# MCU.net
KiCad netlist of a schematic drawn in Altium Designer
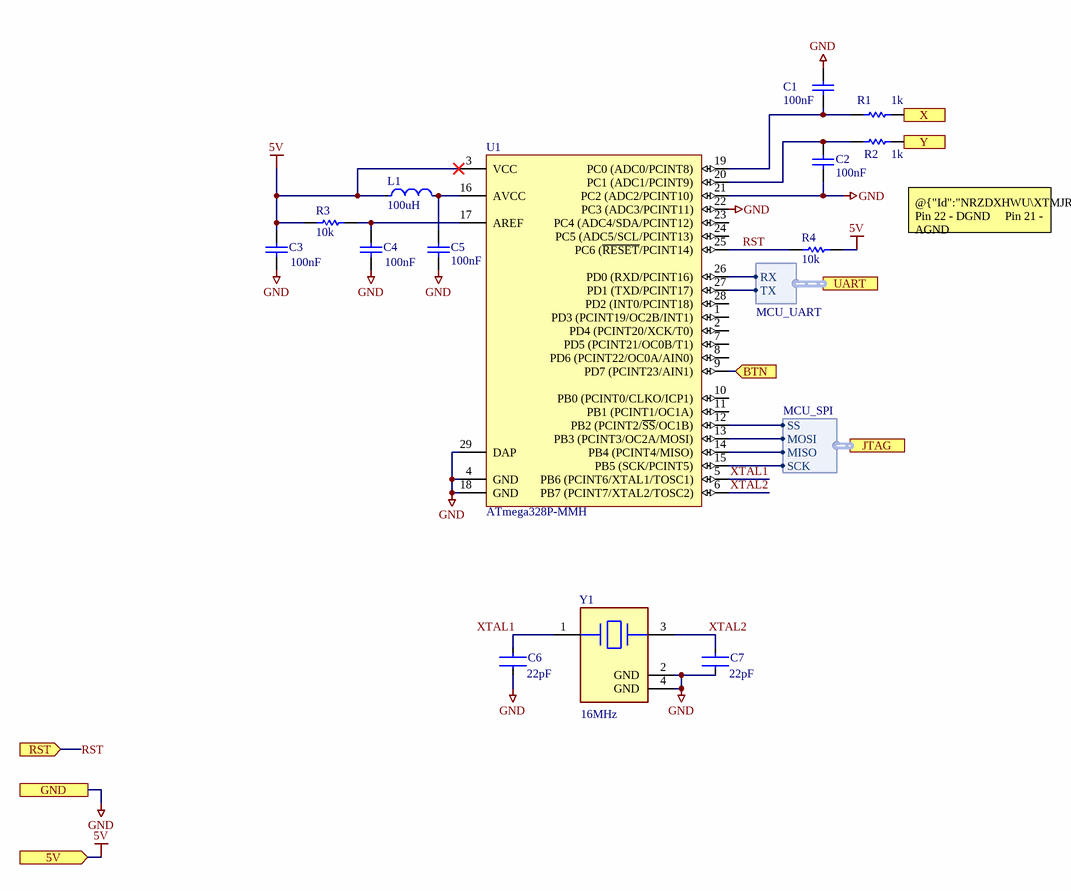
[diagram p0: MCU.SchDoc]

(export (version "E")
  (design (tool "Eeschema 10.0.6"))
  (components
    (comp (ref "C1")
      (value "100nF")
      (footprint "CAPC1005X56X25ML10T15")
      (fields
        (field (name "MANUFACTURER") "AVX Interconnect / Elco")
        (field (name "PART NUMBER") "0402YG104ZAT2A")
      )
      (libsource (lib "Altium Content Vault") (part "CAP"))
    )
    (comp (ref "C2")
      (value "100nF")
      (footprint "CAPC1005X56X25ML10T15")
      (fields
        (field (name "MANUFACTURER") "AVX Interconnect / Elco")
        (field (name "PART NUMBER") "0402YG104ZAT2A")
      )
      (libsource (lib "Altium Content Vault") (part "CAP"))
    )
    (comp (ref "C3")
      (value "100nF")
      (footprint "CAPC1005X56X25ML10T15")
      (fields
        (field (name "MANUFACTURER") "AVX Interconnect / Elco")
        (field (name "PART NUMBER") "0402YG104ZAT2A")
      )
      (libsource (lib "Altium Content Vault") (part "CAP"))
    )
    (comp (ref "C4")
      (value "100nF")
      (footprint "CAPC1005X56X25ML10T15")
      (fields
        (field (name "MANUFACTURER") "AVX Interconnect / Elco")
        (field (name "PART NUMBER") "0402YG104ZAT2A")
      )
      (libsource (lib "Altium Content Vault") (part "CAP"))
    )
    (comp (ref "C5")
      (value "100nF")
      (footprint "CAPC1005X56X25ML10T15")
      (fields
        (field (name "MANUFACTURER") "AVX Interconnect / Elco")
        (field (name "PART NUMBER") "0402YG104ZAT2A")
      )
      (libsource (lib "Altium Content Vault") (part "CAP"))
    )
    (comp (ref "C6")
      (value "C0805C220J5GACTU")
      (footprint "FP-C0805C-DN-MFG")
      (description "Capacitor; Ceramic; Cap; 22.0pF; Tol 5%; SMT; Vol-Rtg 50V; C0G; Tape and Reel")
      (fields
        (field (name "OCTOPART") "https://octopart.com/c0805c220j5gactu-kemet-145470")
        (field (name "MANUFACTURER") "KEMET")
      )
      (libsource (lib "Altium Content Vault") (part "b4654b650e69147ec39a6b967a45e02"))
    )
    (comp (ref "C7")
      (value "C0805C220J5GACTU")
      (footprint "FP-C0805C-DN-MFG")
      (description "Capacitor; Ceramic; Cap; 22.0pF; Tol 5%; SMT; Vol-Rtg 50V; C0G; Tape and Reel")
      (fields
        (field (name "OCTOPART") "https://octopart.com/c0805c220j5gactu-kemet-145470")
        (field (name "MANUFACTURER") "KEMET")
      )
      (libsource (lib "Altium Content Vault") (part "b4654b650e69147ec39a6b967a45e02"))
    )
    (comp (ref "L1")
      (value "100uH")
      (footprint "FP-CB3225-MFG")
      (description "SMD Inductors 100uH ±20% 0.34A 1.82Ω 1210")
      (fields (field (name "TOLERANCE") "20%"))
      (libsource (lib "Altium Content Vault") (part "725321dda6339637d4d059423bc1c3c"))
    )
    (comp (ref "R1")
      (value "1k")
      (footprint "RESC1608X55X25ML10T15")
      (fields (field (name "PART NUMBER") "RT0603BRE071KL") (field (name "MANUFACTURER") "Yageo"))
      (libsource (lib "Altium Content Vault") (part "RES"))
    )
    (comp (ref "R2")
      (value "1k")
      (footprint "RESC1608X55X25ML10T15")
      (fields (field (name "PART NUMBER") "RT0603BRE071KL") (field (name "MANUFACTURER") "Yageo"))
      (libsource (lib "Altium Content Vault") (part "RES"))
    )
    (comp (ref "R3")
      (value "10k")
      (footprint "RESC1005X40X25LL05T05")
      (description "Chip Resistor, 10 KOhm, +/- 1%, 0.1 W, -55 to 155 degC, 0402 (1005 Metric), RoHS, Tape and Reel")
      (fields (field (name "TOLERANCE") "1%") (field (name "MANUFACTURER") "Panasonic"))
      (libsource (lib "Altium Content Vault") (part "RES-2"))
    )
    (comp (ref "R4")
      (value "10k")
      (footprint "RESC1005X40X25LL05T05")
      (description "Chip Resistor, 10 KOhm, +/- 1%, 0.1 W, -55 to 155 degC, 0402 (1005 Metric), RoHS, Tape and Reel")
      (fields (field (name "TOLERANCE") "1%") (field (name "MANUFACTURER") "Panasonic"))
      (libsource (lib "Altium Content Vault") (part "RES-2"))
    )
    (comp (ref "U1")
      (value "ATmega328P-MMH")
      (footprint "28M1_N")
      (libsource (lib "Altium Content Vault") (part "MC-8B-ATM48-IL29"))
    )
    (comp (ref "Y1")
      (value "ABM3B-16.000MHZ-10-1-U-T")
      (footprint "FP-ABM3B-MFG")
      (description "Crystal 16MHz ±10ppm 10pF SMD-4 5mm x 3.2mm")
      (fields (field (name "TOLERANCE") "10ppm"))
      (libsource (lib "Altium Content Vault") (part "48e526d86b7f2615d98721063c72f49"))
    )
  )
  (nets
    (net (code "3") (name "/BTN") (class "Default")
      (node (ref "U1") (pin "9") (pinfunction "PD7_(PCINT23/AIN1)_9") (pintype "bidirectional"))
    )
    (net (code "4") (name "/MISO") (class "Default")
      (node (ref "U1") (pin "14") (pinfunction "PB4_(PCINT4/MISO)_14") (pintype "bidirectional"))
    )
    (net (code "5") (name "/MOSI") (class "Default")
      (node (ref "U1") (pin "13") (pinfunction "PB3_(PCINT3/OC2A/MOSI)_13") (pintype "bidirectional"))
    )
    (net (code "6") (name "/RST") (class "Default")
      (node (ref "R4") (pin "2") (pinfunction "2_2") (pintype "passive"))
      (node (ref "U1") (pin "25") (pinfunction "PC6_(~{RESET}/PCINT14)_25") (pintype "bidirectional"))
    )
    (net (code "7") (name "/RX") (class "Default")
      (node (ref "U1") (pin "26") (pinfunction "PD0_(RXD/PCINT16)_26") (pintype "bidirectional"))
    )
    (net (code "8") (name "/SCK") (class "Default")
      (node (ref "U1") (pin "15") (pinfunction "PB5_(SCK/PCINT5)_15") (pintype "bidirectional"))
    )
    (net (code "9") (name "/SS") (class "Default")
      (node (ref "U1") (pin "12") (pinfunction "PB2_(PCINT2/~{SS}/OC1B)_12") (pintype "bidirectional"))
    )
    (net (code "10") (name "/TX") (class "Default")
      (node (ref "U1") (pin "27") (pinfunction "PD1_(TXD/PCINT17)_27") (pintype "bidirectional"))
    )
    (net (code "11") (name "/X") (class "Default")
      (node (ref "R1") (pin "2") (pinfunction "2_2") (pintype "passive"))
    )
    (net (code "12") (name "/XTAL1") (class "Default")
      (node (ref "C6") (pin "1") (pinfunction "1_1") (pintype "passive"))
      (node (ref "U1") (pin "5") (pinfunction "PB6_(PCINT6/XTAL1/TOSC1)_5") (pintype "bidirectional"))
      (node (ref "Y1") (pin "1") (pinfunction "1_1") (pintype "passive"))
    )
    (net (code "13") (name "/XTAL2") (class "Default")
      (node (ref "C7") (pin "1") (pinfunction "1_1") (pintype "passive"))
      (node (ref "U1") (pin "6") (pinfunction "PB7_(PCINT7/XTAL2/TOSC2)_6") (pintype "bidirectional"))
      (node (ref "Y1") (pin "3") (pinfunction "3_3") (pintype "passive"))
    )
    (net (code "14") (name "/Y") (class "Default")
      (node (ref "R2") (pin "2") (pinfunction "2_2") (pintype "passive"))
    )
    (net (code "17") (name "5V") (class "Default")
      (node (ref "C3") (pin "2") (pinfunction "2_2") (pintype "passive"))
      (node (ref "L1") (pin "1") (pinfunction "1_1") (pintype "passive"))
      (node (ref "R3") (pin "2") (pinfunction "2_2") (pintype "passive"))
      (node (ref "R4") (pin "1") (pinfunction "1_1") (pintype "passive"))
      (node (ref "U1") (pin "3") (pinfunction "VCC_3") (pintype "power_in"))
    )
    (net (code "18") (name "GND") (class "Default")
      (node (ref "C1") (pin "2") (pinfunction "2_2") (pintype "passive"))
      (node (ref "C2") (pin "2") (pinfunction "2_2") (pintype "passive"))
      (node (ref "C3") (pin "1") (pinfunction "1_1") (pintype "passive"))
      (node (ref "C4") (pin "1") (pinfunction "1_1") (pintype "passive"))
      (node (ref "C5") (pin "2") (pinfunction "2_2") (pintype "passive"))
      (node (ref "C6") (pin "2") (pinfunction "2_2") (pintype "passive"))
      (node (ref "C7") (pin "2") (pinfunction "2_2") (pintype "passive"))
      (node (ref "U1") (pin "18") (pinfunction "GND_18") (pintype "power_in"))
      (node (ref "U1") (pin "21") (pinfunction "PC2_(ADC2/PCINT10)_21") (pintype "bidirectional"))
      (node (ref "U1") (pin "22") (pinfunction "PC3_(ADC3/PCINT11)_22") (pintype "bidirectional"))
      (node (ref "U1") (pin "29") (pinfunction "DAP_29") (pintype "power_in"))
      (node (ref "U1") (pin "4") (pinfunction "GND_4") (pintype "power_in"))
      (node (ref "Y1") (pin "2") (pinfunction "GND_2") (pintype "power_in"))
      (node (ref "Y1") (pin "4") (pinfunction "GND_4") (pintype "power_in"))
    )
    (net (code "19") (name "Net-(U1-AREF)") (class "Default")
      (node (ref "C4") (pin "2") (pinfunction "2_2") (pintype "passive"))
      (node (ref "R3") (pin "1") (pinfunction "1_1") (pintype "passive"))
      (node (ref "U1") (pin "17") (pinfunction "AREF_17") (pintype "power_in"))
    )
    (net (code "20") (name "Net-(U1-AVCC)") (class "Default")
      (node (ref "C5") (pin "1") (pinfunction "1_1") (pintype "passive"))
      (node (ref "L1") (pin "2") (pinfunction "2_2") (pintype "passive"))
      (node (ref "U1") (pin "16") (pinfunction "AVCC_16") (pintype "power_in"))
    )
    (net (code "21") (name "Net-(U1-PC0_(ADC0{slash}PCINT8))") (class "Default")
      (node (ref "C1") (pin "1") (pinfunction "1_1") (pintype "passive"))
      (node (ref "R1") (pin "1") (pinfunction "1_1") (pintype "passive"))
      (node (ref "U1") (pin "19") (pinfunction "PC0_(ADC0/PCINT8)_19") (pintype "bidirectional"))
    )
    (net (code "22") (name "Net-(U1-PC1_(ADC1{slash}PCINT9))") (class "Default")
      (node (ref "C2") (pin "1") (pinfunction "1_1") (pintype "passive"))
      (node (ref "R2") (pin "1") (pinfunction "1_1") (pintype "passive"))
      (node (ref "U1") (pin "20") (pinfunction "PC1_(ADC1/PCINT9)_20") (pintype "bidirectional"))
    )
    (net (code "23") (name "unconnected-(U1-PB0_(PCINT0{slash}CLKO{slash}ICP1)-Pad10)") (class "Default")
      (node (ref "U1") (pin "10") (pinfunction "PB0_(PCINT0/CLKO/ICP1)_10") (pintype "bidirectional"))
    )
    (net (code "24") (name "unconnected-(U1-PB1_(PCINT1{slash}OC1A)-Pad11)") (class "Default")
      (node (ref "U1") (pin "11") (pinfunction "PB1_(PCINT1/OC1A)_11") (pintype "bidirectional"))
    )
    (net (code "25") (name "unconnected-(U1-PC4_(ADC4{slash}SDA{slash}PCINT12)-Pad23)") (class "Default")
      (node (ref "U1") (pin "23") (pinfunction "PC4_(ADC4/SDA/PCINT12)_23") (pintype "bidirectional"))
    )
    (net (code "26") (name "unconnected-(U1-PC5_(ADC5{slash}SCL{slash}PCINT13)-Pad24)") (class "Default")
      (node (ref "U1") (pin "24") (pinfunction "PC5_(ADC5/SCL/PCINT13)_24") (pintype "bidirectional"))
    )
    (net (code "27") (name "unconnected-(U1-PD2_(INT0{slash}PCINT18)-Pad28)") (class "Default")
      (node (ref "U1") (pin "28") (pinfunction "PD2_(INT0/PCINT18)_28") (pintype "bidirectional"))
    )
    (net (code "28") (name "unconnected-(U1-PD3_(PCINT19{slash}OC2B{slash}INT1)-Pad1)") (class "Default")
      (node (ref "U1") (pin "1") (pinfunction "PD3_(PCINT19/OC2B/INT1)_1") (pintype "bidirectional"))
    )
    (net (code "29") (name "unconnected-(U1-PD4_(PCINT20{slash}XCK{slash}T0)-Pad2)") (class "Default")
      (node (ref "U1") (pin "2") (pinfunction "PD4_(PCINT20/XCK/T0)_2") (pintype "bidirectional"))
    )
    (net (code "30") (name "unconnected-(U1-PD5_(PCINT21{slash}OC0B{slash}T1)-Pad7)") (class "Default")
      (node (ref "U1") (pin "7") (pinfunction "PD5_(PCINT21/OC0B/T1)_7") (pintype "bidirectional"))
    )
    (net (code "31") (name "unconnected-(U1-PD6_(PCINT22{slash}OC0A{slash}AIN0)-Pad8)") (class "Default")
      (node (ref "U1") (pin "8") (pinfunction "PD6_(PCINT22/OC0A/AIN0)_8") (pintype "bidirectional"))
    )
  )
)
